# Arduino_FPGA_Level_Translation.net
KiCad netlist of a schematic drawn in Altium Designer
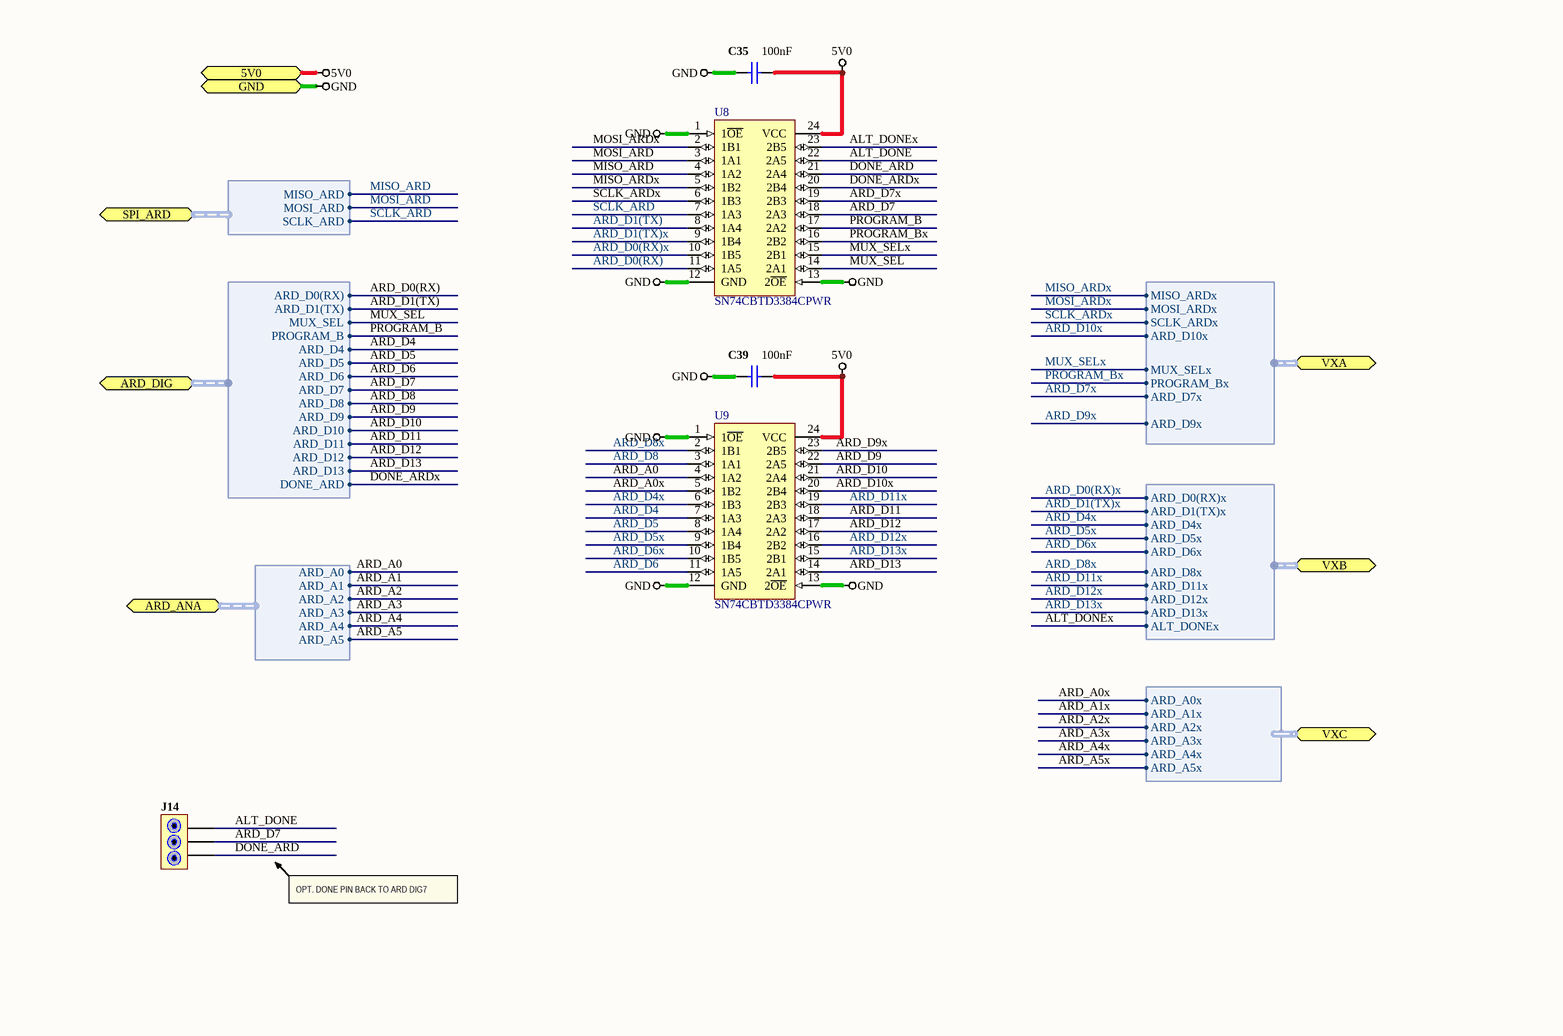
[diagram p0: Arduino FPGA Level Translation.SchDoc]

(export (version "E")
  (design (tool "Eeschema 10.0.6"))
  (components
    (comp (ref "C35")
      (value "100nF")
      (footprint "CAPC0402(1005)60_L")
      (fields
        (field (name "TOLERANCE") "±10%")
        (field (name "MANUFACTURER PART NUMBER") "C0402C104K8PACTU")
        (field (name "Comment") "CAP 100nF 16V 0402(1005)")
      )
      (libsource (lib "Component_Database") (part "CAP_NP"))
    )
    (comp (ref "C39")
      (value "100nF")
      (footprint "CAPC0402(1005)60_L")
      (fields
        (field (name "TOLERANCE") "±10%")
        (field (name "MANUFACTURER PART NUMBER") "C0402C104K8PACTU")
        (field (name "Comment") "CAP 100nF 16V 0402(1005)")
      )
      (libsource (lib "Component_Database") (part "CAP_NP"))
    )
    (comp (ref "J14")
      (value "3-WAY JUMPER")
      (footprint "HDR1X3")
      (description "3-Way Jumper - Center Output")
      (fields (field (name "MANUFACTURER PART NUMBER") "71417-103HLF"))
      (libsource (lib "3-WAY JUMPER") (part "3-WAY JUMPER"))
    )
    (comp (ref "U8")
      (value "SN74CBTD3384CPWR")
      (footprint "TSOP65P620X120-24N")
      (description "10-BIT FET BUS SWITCH WITH LEVEL SHIFTING")
      (fields
        (field (name "MANUFACTURER PART NUMBER") "SN74CBTD3861PWR")
        (field (name "MANUFACTURER") "Texas Instruments")
      )
      (libsource (lib "SN74CBTD3384CPWR") (part "SN74CBTD3384CPWR"))
    )
    (comp (ref "U9")
      (value "SN74CBTD3384CPWR")
      (footprint "TSOP65P620X120-24N")
      (description "10-BIT FET BUS SWITCH WITH LEVEL SHIFTING")
      (fields
        (field (name "MANUFACTURER PART NUMBER") "SN74CBTD3861PWR")
        (field (name "MANUFACTURER") "Texas Instruments")
      )
      (libsource (lib "SN74CBTD3384CPWR") (part "SN74CBTD3384CPWR"))
    )
  )
  (nets
    (net (code "7") (name "/ALT_DONE") (class "Default")
      (node (ref "J14") (pin "3") (pinfunction "3_3") (pintype "passive"))
      (node (ref "U8") (pin "22") (pinfunction "2A5_22") (pintype "bidirectional"))
    )
    (net (code "8") (name "/ALT_DONEx") (class "Default")
      (node (ref "U8") (pin "23") (pinfunction "2B5_23") (pintype "bidirectional"))
    )
    (net (code "9") (name "/ARD_A0") (class "Default")
      (node (ref "U9") (pin "4") (pinfunction "1A2_4") (pintype "bidirectional"))
    )
    (net (code "10") (name "/ARD_A0x") (class "Default")
      (node (ref "U9") (pin "5") (pinfunction "1B2_5") (pintype "bidirectional"))
    )
    (net (code "21") (name "/ARD_D0(RX)") (class "Default")
      (node (ref "U8") (pin "11") (pinfunction "1A5_11") (pintype "bidirectional"))
    )
    (net (code "22") (name "/ARD_D0(RX)x") (class "Default")
      (node (ref "U8") (pin "10") (pinfunction "1B5_10") (pintype "bidirectional"))
    )
    (net (code "23") (name "/ARD_D1(TX)") (class "Default")
      (node (ref "U8") (pin "8") (pinfunction "1A4_8") (pintype "bidirectional"))
    )
    (net (code "24") (name "/ARD_D1(TX)x") (class "Default")
      (node (ref "U8") (pin "9") (pinfunction "1B4_9") (pintype "bidirectional"))
    )
    (net (code "25") (name "/ARD_D4") (class "Default")
      (node (ref "U9") (pin "7") (pinfunction "1A3_7") (pintype "bidirectional"))
    )
    (net (code "26") (name "/ARD_D4x") (class "Default")
      (node (ref "U9") (pin "6") (pinfunction "1B3_6") (pintype "bidirectional"))
    )
    (net (code "27") (name "/ARD_D5") (class "Default")
      (node (ref "U9") (pin "8") (pinfunction "1A4_8") (pintype "bidirectional"))
    )
    (net (code "28") (name "/ARD_D5x") (class "Default")
      (node (ref "U9") (pin "9") (pinfunction "1B4_9") (pintype "bidirectional"))
    )
    (net (code "29") (name "/ARD_D6") (class "Default")
      (node (ref "U9") (pin "11") (pinfunction "1A5_11") (pintype "bidirectional"))
    )
    (net (code "30") (name "/ARD_D6x") (class "Default")
      (node (ref "U9") (pin "10") (pinfunction "1B5_10") (pintype "bidirectional"))
    )
    (net (code "31") (name "/ARD_D7") (class "Default")
      (node (ref "J14") (pin "2") (pinfunction "2_2") (pintype "passive"))
      (node (ref "U8") (pin "18") (pinfunction "2A3_18") (pintype "bidirectional"))
    )
    (net (code "32") (name "/ARD_D7x") (class "Default")
      (node (ref "U8") (pin "19") (pinfunction "2B3_19") (pintype "bidirectional"))
    )
    (net (code "33") (name "/ARD_D8") (class "Default")
      (node (ref "U9") (pin "3") (pinfunction "1A1_3") (pintype "bidirectional"))
    )
    (net (code "34") (name "/ARD_D8x") (class "Default")
      (node (ref "U9") (pin "2") (pinfunction "1B1_2") (pintype "bidirectional"))
    )
    (net (code "35") (name "/ARD_D9") (class "Default")
      (node (ref "U9") (pin "22") (pinfunction "2A5_22") (pintype "bidirectional"))
    )
    (net (code "36") (name "/ARD_D9x") (class "Default")
      (node (ref "U9") (pin "23") (pinfunction "2B5_23") (pintype "bidirectional"))
    )
    (net (code "37") (name "/ARD_D10") (class "Default")
      (node (ref "U9") (pin "21") (pinfunction "2A4_21") (pintype "bidirectional"))
    )
    (net (code "38") (name "/ARD_D10x") (class "Default")
      (node (ref "U9") (pin "20") (pinfunction "2B4_20") (pintype "bidirectional"))
    )
    (net (code "39") (name "/ARD_D11") (class "Default")
      (node (ref "U9") (pin "18") (pinfunction "2A3_18") (pintype "bidirectional"))
    )
    (net (code "40") (name "/ARD_D11x") (class "Default")
      (node (ref "U9") (pin "19") (pinfunction "2B3_19") (pintype "bidirectional"))
    )
    (net (code "41") (name "/ARD_D12") (class "Default")
      (node (ref "U9") (pin "17") (pinfunction "2A2_17") (pintype "bidirectional"))
    )
    (net (code "42") (name "/ARD_D12x") (class "Default")
      (node (ref "U9") (pin "16") (pinfunction "2B2_16") (pintype "bidirectional"))
    )
    (net (code "43") (name "/ARD_D13") (class "Default")
      (node (ref "U9") (pin "14") (pinfunction "2A1_14") (pintype "bidirectional"))
    )
    (net (code "44") (name "/ARD_D13x") (class "Default")
      (node (ref "U9") (pin "15") (pinfunction "2B1_15") (pintype "bidirectional"))
    )
    (net (code "45") (name "/DONE_ARD") (class "Default")
      (node (ref "J14") (pin "1") (pinfunction "1_1") (pintype "passive"))
      (node (ref "U8") (pin "21") (pinfunction "2A4_21") (pintype "bidirectional"))
    )
    (net (code "46") (name "/DONE_ARDx") (class "Default")
      (node (ref "U8") (pin "20") (pinfunction "2B4_20") (pintype "bidirectional"))
    )
    (net (code "47") (name "/MISO_ARD") (class "Default")
      (node (ref "U8") (pin "4") (pinfunction "1A2_4") (pintype "bidirectional"))
    )
    (net (code "48") (name "/MISO_ARDx") (class "Default")
      (node (ref "U8") (pin "5") (pinfunction "1B2_5") (pintype "bidirectional"))
    )
    (net (code "49") (name "/MOSI_ARD") (class "Default")
      (node (ref "U8") (pin "3") (pinfunction "1A1_3") (pintype "bidirectional"))
    )
    (net (code "50") (name "/MOSI_ARDx") (class "Default")
      (node (ref "U8") (pin "2") (pinfunction "1B1_2") (pintype "bidirectional"))
    )
    (net (code "51") (name "/MUX_SEL") (class "Default")
      (node (ref "U8") (pin "14") (pinfunction "2A1_14") (pintype "bidirectional"))
    )
    (net (code "52") (name "/MUX_SELx") (class "Default")
      (node (ref "U8") (pin "15") (pinfunction "2B1_15") (pintype "bidirectional"))
    )
    (net (code "53") (name "/PROGRAM_B") (class "Default")
      (node (ref "U8") (pin "17") (pinfunction "2A2_17") (pintype "bidirectional"))
    )
    (net (code "54") (name "/PROGRAM_Bx") (class "Default")
      (node (ref "U8") (pin "16") (pinfunction "2B2_16") (pintype "bidirectional"))
    )
    (net (code "55") (name "/SCLK_ARD") (class "Default")
      (node (ref "U8") (pin "7") (pinfunction "1A3_7") (pintype "bidirectional"))
    )
    (net (code "56") (name "/SCLK_ARDx") (class "Default")
      (node (ref "U8") (pin "6") (pinfunction "1B3_6") (pintype "bidirectional"))
    )
    (net (code "63") (name "5V0") (class "Default")
      (node (ref "C35") (pin "2") (pinfunction "2_2") (pintype "passive"))
      (node (ref "C39") (pin "2") (pinfunction "2_2") (pintype "passive"))
      (node (ref "U8") (pin "24") (pinfunction "VCC_24") (pintype "passive"))
      (node (ref "U9") (pin "24") (pinfunction "VCC_24") (pintype "passive"))
    )
    (net (code "64") (name "GND") (class "Default")
      (node (ref "C35") (pin "1") (pinfunction "1_1") (pintype "passive"))
      (node (ref "C39") (pin "1") (pinfunction "1_1") (pintype "passive"))
      (node (ref "U8") (pin "1") (pinfunction "1~{OE}_1") (pintype "input"))
      (node (ref "U8") (pin "12") (pinfunction "GND_12") (pintype "passive"))
      (node (ref "U8") (pin "13") (pinfunction "2~{OE}_13") (pintype "input"))
      (node (ref "U9") (pin "1") (pinfunction "1~{OE}_1") (pintype "input"))
      (node (ref "U9") (pin "12") (pinfunction "GND_12") (pintype "passive"))
      (node (ref "U9") (pin "13") (pinfunction "2~{OE}_13") (pintype "input"))
    )
  )
)
